# Relay.net
KiCad netlist of a schematic drawn in Altium Designer
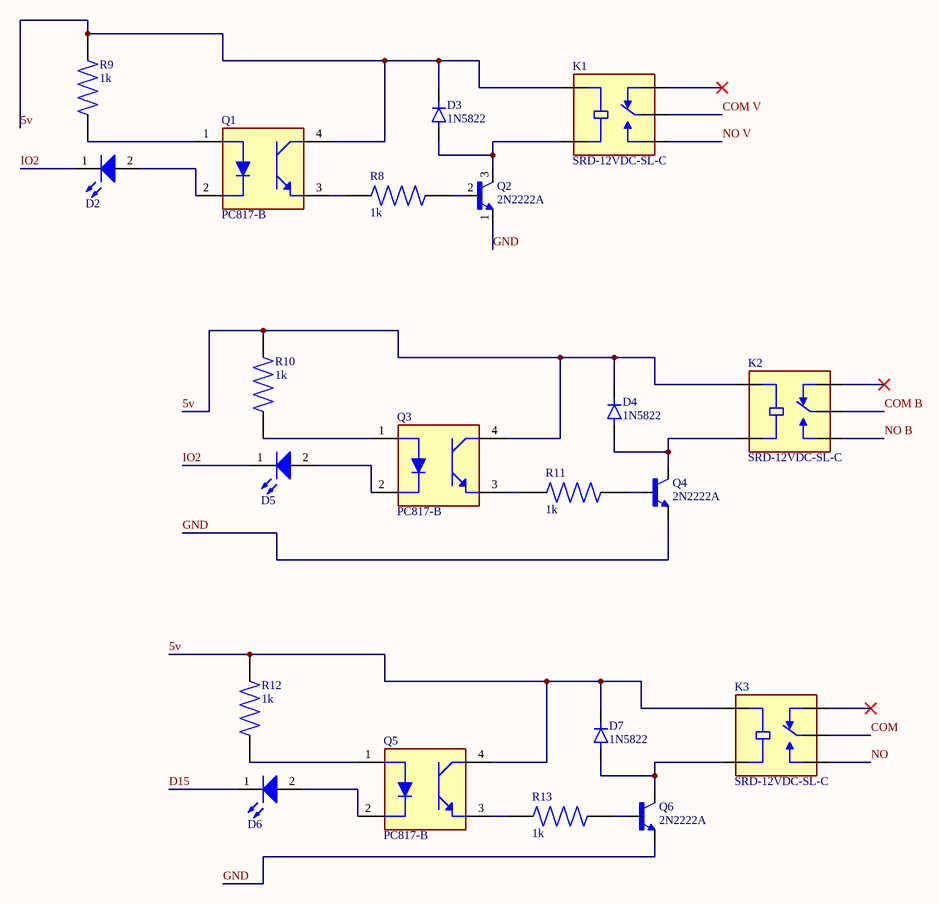
[diagram p0: Relay.SchDoc]

(export (version "E")
  (design (tool "Eeschema 10.0.6"))
  (components
    (comp (ref "D2")
      (value "Blue, 2.8V, 30°")
      (footprint "WL-TMRW_D3.9H10.5")
      (description "WL-TMRW Mono-color Round Waterclear, THT, D3.9 x H10.5mm, Blue, 2.8V, 30°")
      (fields
        (field (name "MANUFACTURER PART NUMBER") "151033BS03000")
        (field (name "MANUFACTURER") "Wurth Elektronik")
      )
      (libsource (lib "WL-TMRW+(rev22b)") (part "151033BS03000"))
    )
    (comp (ref "D3")
      (value "1N5822")
      (footprint "DIOAD1990W125L900D530")
      (description "3A, 40V, Planar Schottky")
      (fields (field (name "MF") "Taiwan Semiconductor"))
      (libsource (lib "1N5822") (part "1N5822"))
    )
    (comp (ref "D4")
      (value "1N5822")
      (footprint "DIOAD1990W125L900D530")
      (description "3A, 40V, Planar Schottky")
      (fields (field (name "MF") "Taiwan Semiconductor"))
      (libsource (lib "1N5822") (part "1N5822"))
    )
    (comp (ref "D5")
      (value "Blue, 2.8V, 30°")
      (footprint "WL-TMRW_D3.9H10.5")
      (description "WL-TMRW Mono-color Round Waterclear, THT, D3.9 x H10.5mm, Blue, 2.8V, 30°")
      (fields
        (field (name "MANUFACTURER PART NUMBER") "151033BS03000")
        (field (name "MANUFACTURER") "Wurth Elektronik")
      )
      (libsource (lib "WL-TMRW+(rev22b)") (part "151033BS03000"))
    )
    (comp (ref "D6")
      (value "Blue, 2.8V, 30°")
      (footprint "WL-TMRW_D3.9H10.5")
      (description "WL-TMRW Mono-color Round Waterclear, THT, D3.9 x H10.5mm, Blue, 2.8V, 30°")
      (fields
        (field (name "MANUFACTURER PART NUMBER") "151033BS03000")
        (field (name "MANUFACTURER") "Wurth Elektronik")
      )
      (libsource (lib "WL-TMRW+(rev22b)") (part "151033BS03000"))
    )
    (comp (ref "D7")
      (value "1N5822")
      (footprint "DIOAD1990W125L900D530")
      (description "3A, 40V, Planar Schottky")
      (fields (field (name "MF") "Taiwan Semiconductor"))
      (libsource (lib "1N5822") (part "1N5822"))
    )
    (comp (ref "K1")
      (value "SRD-12VDC-SL-C")
      (footprint "RELAY_SRD-12VDC-SL-C")
      (description "General Purpose Non Latching 12VDC SPDT Through Hole Relays RoHS")
      (fields (field (name "MF") "Songle Relay"))
      (libsource (lib "SRD-12VDC-SL-C") (part "SRD-12VDC-SL-C"))
    )
    (comp (ref "K2")
      (value "SRD-12VDC-SL-C")
      (footprint "RELAY_SRD-12VDC-SL-C")
      (description "General Purpose Non Latching 12VDC SPDT Through Hole Relays RoHS")
      (fields (field (name "MF") "Songle Relay"))
      (libsource (lib "SRD-12VDC-SL-C") (part "SRD-12VDC-SL-C"))
    )
    (comp (ref "K3")
      (value "SRD-12VDC-SL-C")
      (footprint "RELAY_SRD-12VDC-SL-C")
      (description "General Purpose Non Latching 12VDC SPDT Through Hole Relays RoHS")
      (fields (field (name "MF") "Songle Relay"))
      (libsource (lib "SRD-12VDC-SL-C") (part "SRD-12VDC-SL-C"))
    )
    (comp (ref "Q1")
      (value "PC817-B")
      (footprint "PC817")
      (description "Phototransistors 4-DIP (0.300, 7.62mm)")
      (fields (field (name "MF") "American Bright"))
      (libsource (lib "PC817-B") (part "PC817-B"))
    )
    (comp (ref "Q2")
      (value "2N2222A")
      (footprint "2N2222A - 1")
      (description "BJT, TO-92, 40V, 600mA, NPN, 0.625W, 150Â°C")
      (fields (field (name "MF") "Diotec Semiconductor"))
      (libsource (lib "") (part "2N2222A_1"))
    )
    (comp (ref "Q3")
      (value "PC817-B")
      (footprint "PC817")
      (description "Phototransistors 4-DIP (0.300, 7.62mm)")
      (fields (field (name "MF") "American Bright"))
      (libsource (lib "PC817-B") (part "PC817-B"))
    )
    (comp (ref "Q4")
      (value "2N2222A")
      (footprint "2N2222A - 1")
      (description "BJT, TO-92, 40V, 600mA, NPN, 0.625W, 150Â°C")
      (fields (field (name "MF") "Diotec Semiconductor"))
      (libsource (lib "2N2222A") (part "2N2222A"))
    )
    (comp (ref "Q5")
      (value "PC817-B")
      (footprint "PC817")
      (description "Phototransistors 4-DIP (0.300, 7.62mm)")
      (fields (field (name "MF") "American Bright"))
      (libsource (lib "PC817-B") (part "PC817-B"))
    )
    (comp (ref "Q6")
      (value "2N2222A")
      (footprint "2N2222A - 1")
      (description "BJT, TO-92, 40V, 600mA, NPN, 0.625W, 150Â°C")
      (fields (field (name "MF") "Diotec Semiconductor"))
      (libsource (lib "2N2222A") (part "2N2222A"))
    )
    (comp (ref "R8")
      (value "1k")
      (footprint "RESC2012X60N")
      (description "910 Ohms Â±1% 0.125W, 1/8W Chip Resistor 0805 (2012 Metric) Moisture Resistant Thick Film")
      (fields (field (name "MF") "Yageo") (field (name "MP") "RC0805FR-07910RL"))
      (libsource (lib "RC0805FR-07910RL") (part "RC0805FR-07910RL"))
    )
    (comp (ref "R9")
      (value "1k")
      (footprint "RESC2012X60N")
      (description "910 Ohms Â±1% 0.125W, 1/8W Chip Resistor 0805 (2012 Metric) Moisture Resistant Thick Film")
      (fields (field (name "MF") "Yageo") (field (name "MP") "RC0805FR-07910RL"))
      (libsource (lib "RC0805FR-07910RL") (part "RC0805FR-07910RL"))
    )
    (comp (ref "R10")
      (value "1k")
      (footprint "RESC2012X60N")
      (description "910 Ohms Â±1% 0.125W, 1/8W Chip Resistor 0805 (2012 Metric) Moisture Resistant Thick Film")
      (fields (field (name "MF") "Yageo") (field (name "MP") "RC0805FR-07910RL"))
      (libsource (lib "RC0805FR-07910RL") (part "RC0805FR-07910RL"))
    )
    (comp (ref "R11")
      (value "1k")
      (footprint "RESC2012X60N")
      (description "910 Ohms Â±1% 0.125W, 1/8W Chip Resistor 0805 (2012 Metric) Moisture Resistant Thick Film")
      (fields (field (name "MF") "Yageo") (field (name "MP") "RC0805FR-07910RL"))
      (libsource (lib "RC0805FR-07910RL") (part "RC0805FR-07910RL"))
    )
    (comp (ref "R12")
      (value "1k")
      (footprint "RESC2012X60N")
      (description "910 Ohms Â±1% 0.125W, 1/8W Chip Resistor 0805 (2012 Metric) Moisture Resistant Thick Film")
      (fields (field (name "MF") "Yageo") (field (name "MP") "RC0805FR-07910RL"))
      (libsource (lib "RC0805FR-07910RL") (part "RC0805FR-07910RL"))
    )
    (comp (ref "R13")
      (value "1k")
      (footprint "RESC2012X60N")
      (description "910 Ohms Â±1% 0.125W, 1/8W Chip Resistor 0805 (2012 Metric) Moisture Resistant Thick Film")
      (fields (field (name "MF") "Yageo") (field (name "MP") "RC0805FR-07910RL"))
      (libsource (lib "RC0805FR-07910RL") (part "RC0805FR-07910RL"))
    )
  )
  (nets
    (net (code "1") (name "/5v") (class "Default")
      (node (ref "D3") (pin "C") (pinfunction "K_C") (pintype "passive"))
      (node (ref "D4") (pin "C") (pinfunction "K_C") (pintype "passive"))
      (node (ref "D7") (pin "C") (pinfunction "K_C") (pintype "passive"))
      (node (ref "K1") (pin "COIL1") (pinfunction "COIL1_COIL1") (pintype "passive"))
      (node (ref "K2") (pin "COIL1") (pinfunction "COIL1_COIL1") (pintype "passive"))
      (node (ref "K3") (pin "COIL1") (pinfunction "COIL1_COIL1") (pintype "passive"))
      (node (ref "Q1") (pin "4") (pinfunction "COLLECTOR_4") (pintype "passive"))
      (node (ref "Q3") (pin "4") (pinfunction "COLLECTOR_4") (pintype "passive"))
      (node (ref "Q5") (pin "4") (pinfunction "COLLECTOR_4") (pintype "passive"))
      (node (ref "R10") (pin "1") (pinfunction "1_1") (pintype "passive"))
      (node (ref "R12") (pin "1") (pinfunction "1_1") (pintype "passive"))
      (node (ref "R9") (pin "1") (pinfunction "1_1") (pintype "passive"))
    )
    (net (code "2") (name "/COM") (class "Default")
      (node (ref "K3") (pin "COM") (pinfunction "COM_COM") (pintype "passive"))
    )
    (net (code "3") (name "/COM B") (class "Default")
      (node (ref "K2") (pin "COM") (pinfunction "COM_COM") (pintype "passive"))
    )
    (net (code "4") (name "/COM V") (class "Default")
      (node (ref "K1") (pin "COM") (pinfunction "COM_COM") (pintype "passive"))
    )
    (net (code "5") (name "/D15") (class "Default")
      (node (ref "D6") (pin "1") (pinfunction "K_1") (pintype "passive"))
    )
    (net (code "6") (name "/GND") (class "Default")
      (node (ref "Q2") (pin "1") (pinfunction "E_1") (pintype "passive"))
      (node (ref "Q4") (pin "1") (pinfunction "E_1") (pintype "passive"))
      (node (ref "Q6") (pin "1") (pinfunction "E_1") (pintype "passive"))
    )
    (net (code "7") (name "/IO2") (class "Default")
      (node (ref "D2") (pin "1") (pinfunction "K_1") (pintype "passive"))
      (node (ref "D5") (pin "1") (pinfunction "K_1") (pintype "passive"))
    )
    (net (code "8") (name "/NO") (class "Default")
      (node (ref "K3") (pin "NO") (pinfunction "NO_NO") (pintype "passive"))
    )
    (net (code "9") (name "/NO B") (class "Default")
      (node (ref "K2") (pin "NO") (pinfunction "NO_NO") (pintype "passive"))
    )
    (net (code "10") (name "/NO V") (class "Default")
      (node (ref "K1") (pin "NO") (pinfunction "NO_NO") (pintype "passive"))
    )
    (net (code "11") (name "Net-(D2-A)") (class "Default")
      (node (ref "D2") (pin "2") (pinfunction "A_2") (pintype "passive"))
      (node (ref "Q1") (pin "2") (pinfunction "CATHODE_2") (pintype "passive"))
    )
    (net (code "12") (name "Net-(D5-A)") (class "Default")
      (node (ref "D5") (pin "2") (pinfunction "A_2") (pintype "passive"))
      (node (ref "Q3") (pin "2") (pinfunction "CATHODE_2") (pintype "passive"))
    )
    (net (code "13") (name "Net-(D6-A)") (class "Default")
      (node (ref "D6") (pin "2") (pinfunction "A_2") (pintype "passive"))
      (node (ref "Q5") (pin "2") (pinfunction "CATHODE_2") (pintype "passive"))
    )
    (net (code "14") (name "Net-(Q1-ANODE)") (class "Default")
      (node (ref "Q1") (pin "1") (pinfunction "ANODE_1") (pintype "passive"))
      (node (ref "R9") (pin "2") (pinfunction "2_2") (pintype "passive"))
    )
    (net (code "15") (name "Net-(Q1-EMITTER)") (class "Default")
      (node (ref "Q1") (pin "3") (pinfunction "EMITTER_3") (pintype "passive"))
      (node (ref "R8") (pin "1") (pinfunction "1_1") (pintype "passive"))
    )
    (net (code "16") (name "Net-(Q2-B)") (class "Default")
      (node (ref "Q2") (pin "2") (pinfunction "B_2") (pintype "passive"))
      (node (ref "R8") (pin "2") (pinfunction "2_2") (pintype "passive"))
    )
    (net (code "17") (name "Net-(Q2-C)") (class "Default")
      (node (ref "D3") (pin "A") (pinfunction "A_A") (pintype "passive"))
      (node (ref "K1") (pin "COIL2") (pinfunction "COIL2_COIL2") (pintype "passive"))
      (node (ref "Q2") (pin "3") (pinfunction "C_3") (pintype "passive"))
    )
    (net (code "18") (name "Net-(Q3-ANODE)") (class "Default")
      (node (ref "Q3") (pin "1") (pinfunction "ANODE_1") (pintype "passive"))
      (node (ref "R10") (pin "2") (pinfunction "2_2") (pintype "passive"))
    )
    (net (code "19") (name "Net-(Q3-EMITTER)") (class "Default")
      (node (ref "Q3") (pin "3") (pinfunction "EMITTER_3") (pintype "passive"))
      (node (ref "R11") (pin "1") (pinfunction "1_1") (pintype "passive"))
    )
    (net (code "20") (name "Net-(Q4-B)") (class "Default")
      (node (ref "Q4") (pin "2") (pinfunction "B_2") (pintype "passive"))
      (node (ref "R11") (pin "2") (pinfunction "2_2") (pintype "passive"))
    )
    (net (code "21") (name "Net-(Q4-C)") (class "Default")
      (node (ref "D4") (pin "A") (pinfunction "A_A") (pintype "passive"))
      (node (ref "K2") (pin "COIL2") (pinfunction "COIL2_COIL2") (pintype "passive"))
      (node (ref "Q4") (pin "3") (pinfunction "C_3") (pintype "passive"))
    )
    (net (code "22") (name "Net-(Q5-ANODE)") (class "Default")
      (node (ref "Q5") (pin "1") (pinfunction "ANODE_1") (pintype "passive"))
      (node (ref "R12") (pin "2") (pinfunction "2_2") (pintype "passive"))
    )
    (net (code "23") (name "Net-(Q5-EMITTER)") (class "Default")
      (node (ref "Q5") (pin "3") (pinfunction "EMITTER_3") (pintype "passive"))
      (node (ref "R13") (pin "1") (pinfunction "1_1") (pintype "passive"))
    )
    (net (code "24") (name "Net-(Q6-B)") (class "Default")
      (node (ref "Q6") (pin "2") (pinfunction "B_2") (pintype "passive"))
      (node (ref "R13") (pin "2") (pinfunction "2_2") (pintype "passive"))
    )
    (net (code "25") (name "Net-(Q6-C)") (class "Default")
      (node (ref "D7") (pin "A") (pinfunction "A_A") (pintype "passive"))
      (node (ref "K3") (pin "COIL2") (pinfunction "COIL2_COIL2") (pintype "passive"))
      (node (ref "Q6") (pin "3") (pinfunction "C_3") (pintype "passive"))
    )
    (net (code "26") (name "unconnected-(K1-PadNC)") (class "Default")
      (node (ref "K1") (pin "NC") (pinfunction "NC_NC") (pintype "passive+no_connect"))
    )
    (net (code "27") (name "unconnected-(K2-PadNC)") (class "Default")
      (node (ref "K2") (pin "NC") (pinfunction "NC_NC") (pintype "passive+no_connect"))
    )
    (net (code "28") (name "unconnected-(K3-PadNC)") (class "Default")
      (node (ref "K3") (pin "NC") (pinfunction "NC_NC") (pintype "passive+no_connect"))
    )
  )
)
